# TL2285_labpcb.net
KiCad netlist of a schematic drawn in EAGLE
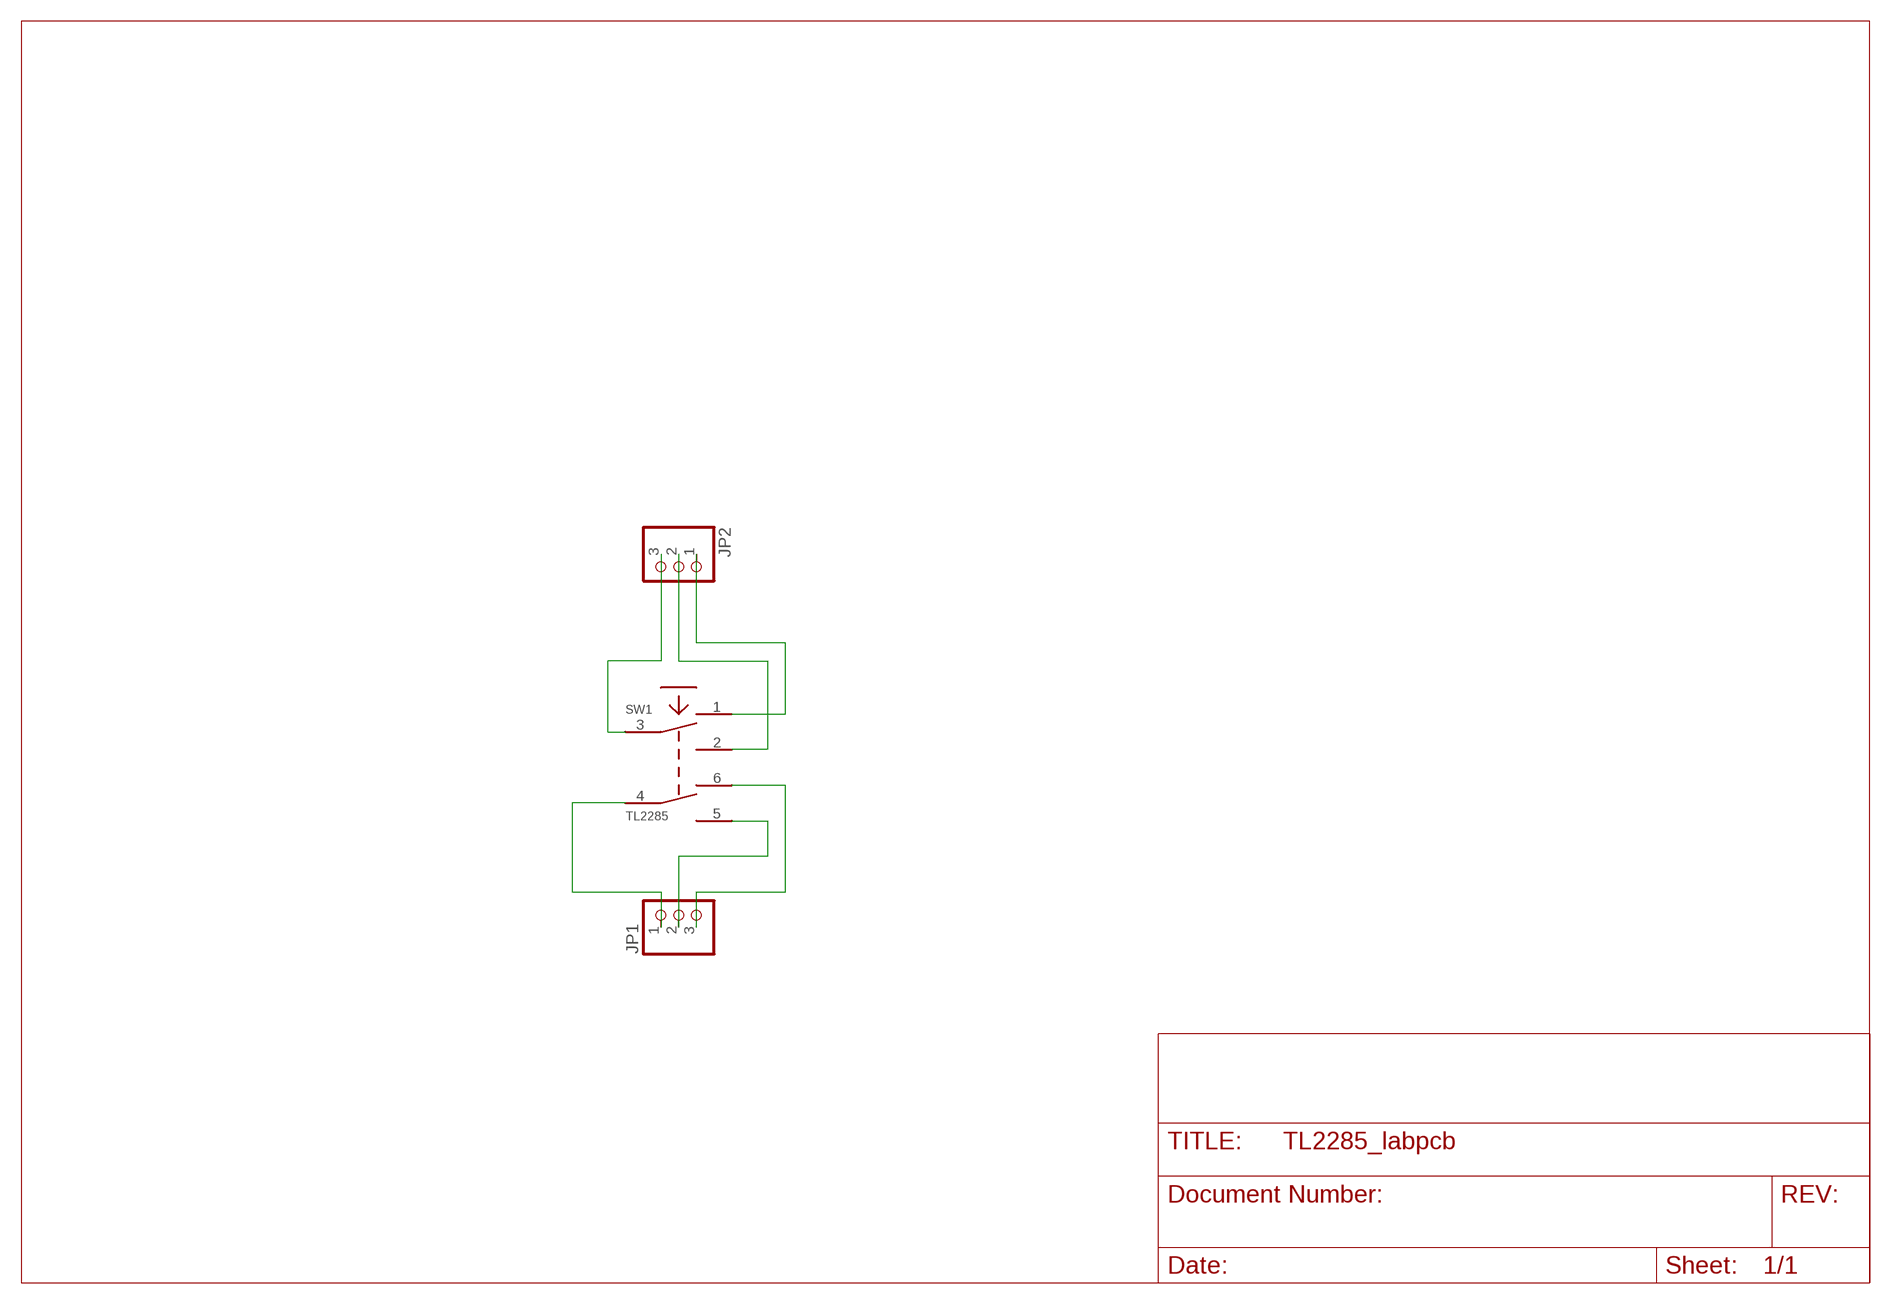
[diagram p0: schematic, sheet 1]

(export (version "E")
  (design (tool "Eeschema 10.0.6"))
  (components
    (comp (ref "JP1")
      (value "PINHD-1X3")
      (footprint "eagle-import:1X03")
      (libsource (lib "eagle-import") (part "PINHD-1X3"))
    )
    (comp (ref "JP2")
      (value "PINHD-1X3")
      (footprint "eagle-import:1X03")
      (libsource (lib "eagle-import") (part "PINHD-1X3"))
    )
    (comp (ref "SW1")
      (value "TL2285")
      (footprint "eagle-import:TL2285_PCB")
      (libsource (lib "eagle-import") (part "TL2285"))
    )
  )
  (nets
    (net (code "1") (name "Net-(SW1-P1)") (class "Default")
      (node (ref "JP2") (pin "1") (pinfunction "1_1") (pintype "passive"))
      (node (ref "SW1") (pin "1") (pinfunction "P1_1") (pintype "bidirectional"))
    )
    (net (code "2") (name "Net-(SW1-P2)") (class "Default")
      (node (ref "JP2") (pin "2") (pinfunction "2_2") (pintype "passive"))
      (node (ref "SW1") (pin "2") (pinfunction "P2_2") (pintype "bidirectional"))
    )
    (net (code "3") (name "Net-(SW1-P3)") (class "Default")
      (node (ref "JP2") (pin "3") (pinfunction "3_3") (pintype "passive"))
      (node (ref "SW1") (pin "3") (pinfunction "P3_3") (pintype "bidirectional"))
    )
    (net (code "4") (name "Net-(SW1-P4)") (class "Default")
      (node (ref "JP1") (pin "1") (pinfunction "1_1") (pintype "passive"))
      (node (ref "SW1") (pin "4") (pinfunction "P4_4") (pintype "bidirectional"))
    )
    (net (code "5") (name "Net-(SW1-P5)") (class "Default")
      (node (ref "JP1") (pin "2") (pinfunction "2_2") (pintype "passive"))
      (node (ref "SW1") (pin "5") (pinfunction "P5_5") (pintype "bidirectional"))
    )
    (net (code "6") (name "Net-(SW1-P6)") (class "Default")
      (node (ref "JP1") (pin "3") (pinfunction "3_3") (pintype "passive"))
      (node (ref "SW1") (pin "6") (pinfunction "P6_6") (pintype "bidirectional"))
    )
  )
)
